# ZigBee.net
KiCad netlist of a schematic drawn in Altium Designer
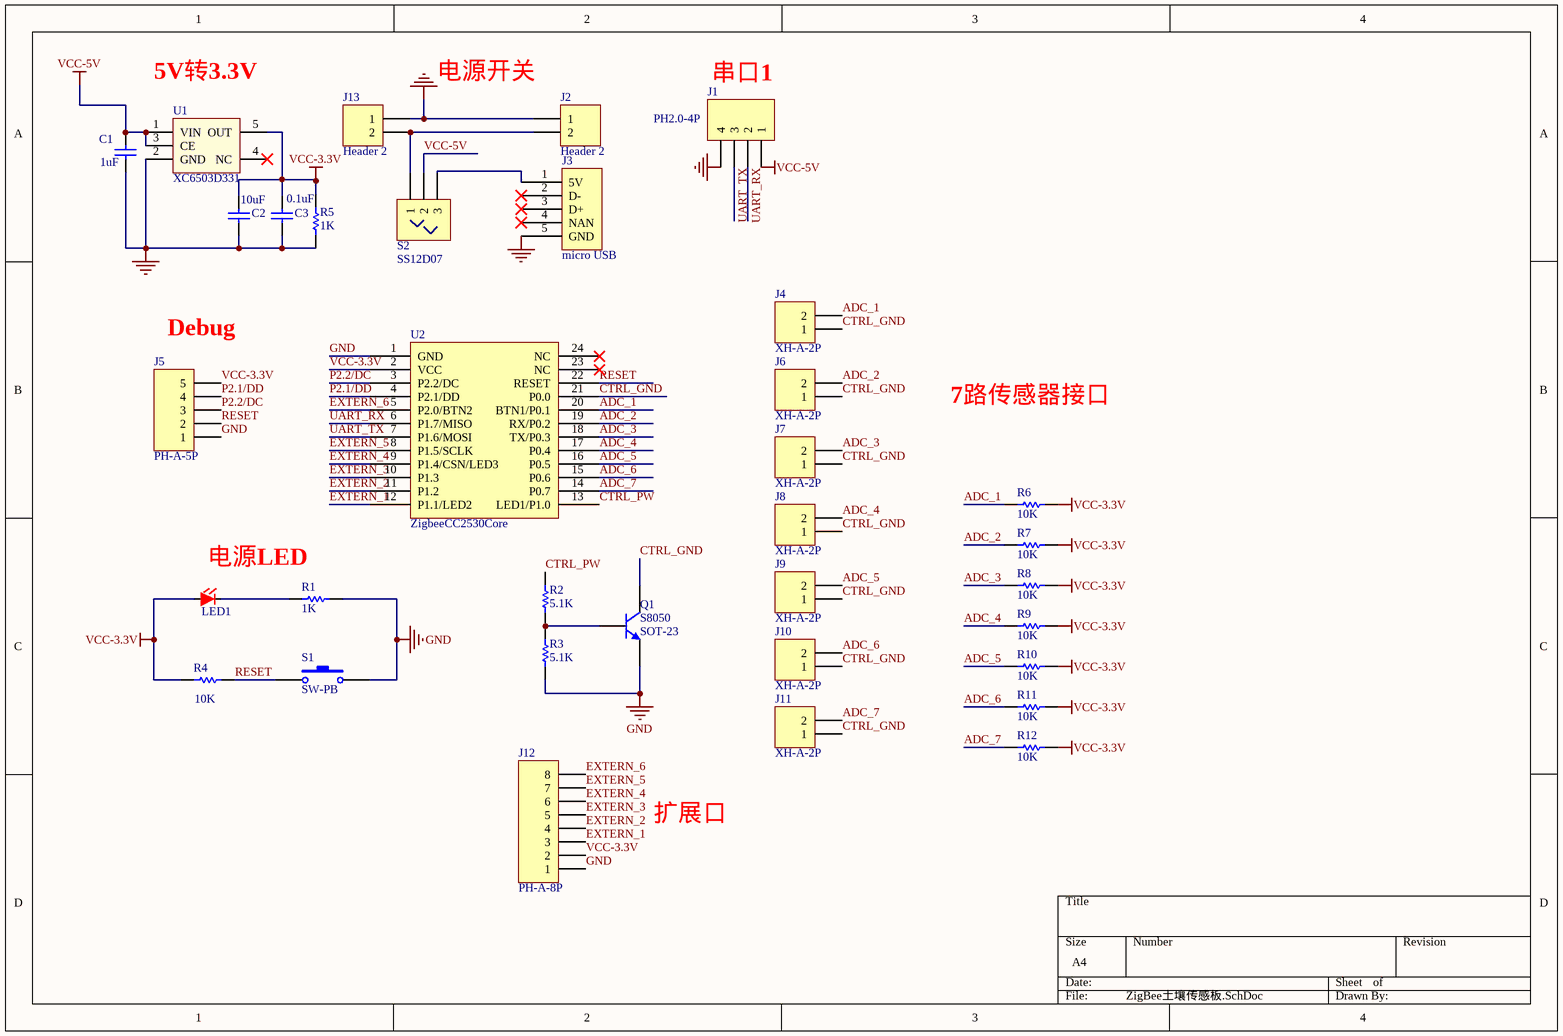
[diagram p0: ZigBee土壤传感板.SchDoc]

(export (version "E")
  (design (tool "Eeschema 10.0.6"))
  (components
    (comp (ref "C1")
      (value "1uF")
      (footprint "C0805_M2013")
      (description "Capacitor")
      (fields (field (name "PUBLISHER") "Altium Limited"))
      (libsource (lib "Miscellaneous Devices") (part "Cap"))
    )
    (comp (ref "C2")
      (value "10uF")
      (footprint "C0805_M2013")
      (description "Capacitor")
      (fields (field (name "PUBLISHER") "Altium Limited"))
      (libsource (lib "Miscellaneous Devices") (part "Cap"))
    )
    (comp (ref "C3")
      (value "0.1uF")
      (footprint "C0805_M2013")
      (description "Capacitor")
      (fields (field (name "PUBLISHER") "Altium Limited"))
      (libsource (lib "Miscellaneous Devices") (part "Cap"))
    )
    (comp (ref "J1")
      (value "PH2.0-4P")
      (footprint "PH2.0-4P")
      (description "Header, 4-Pin")
      (fields (field (name "PUBLISHER") "Altium Limited"))
      (libsource (lib "Miscellaneous Connectors") (part "Header 4"))
    )
    (comp (ref "J2")
      (value "Header 2")
      (footprint "18650")
      (description "Header, 2-Pin")
      (fields (field (name "PUBLISHER") "Altium Limited"))
      (libsource (lib "") (part "Header 2_1"))
    )
    (comp (ref "J3")
      (value "micro USB")
      (footprint "MICRO-USB")
      (description "micro USB母")
      (libsource (lib "Liyao原理图库") (part "micro USB"))
    )
    (comp (ref "J4")
      (value "XH-A-2P")
      (footprint "XH-A-2P")
      (description "Header, 2.5mm,2-Pin")
      (libsource (lib "7.PH XH VH KF2510连接器原理库") (part "XH-A-2P"))
    )
    (comp (ref "J5")
      (value "PH-A-5P")
      (footprint "PH-A-5P")
      (description "Header, 2.0mm,5-Pin")
      (libsource (lib "7.PH XH VH KF2510连接器原理库") (part "PH-A-5P"))
    )
    (comp (ref "J6")
      (value "XH-A-2P")
      (footprint "XH-A-2P")
      (description "Header, 2.5mm,2-Pin")
      (libsource (lib "7.PH XH VH KF2510连接器原理库") (part "XH-A-2P"))
    )
    (comp (ref "J7")
      (value "XH-A-2P")
      (footprint "XH-A-2P")
      (description "Header, 2.5mm,2-Pin")
      (libsource (lib "7.PH XH VH KF2510连接器原理库") (part "XH-A-2P"))
    )
    (comp (ref "J8")
      (value "XH-A-2P")
      (footprint "XH-A-2P")
      (description "Header, 2.5mm,2-Pin")
      (libsource (lib "7.PH XH VH KF2510连接器原理库") (part "XH-A-2P"))
    )
    (comp (ref "J9")
      (value "XH-A-2P")
      (footprint "XH-A-2P")
      (description "Header, 2.5mm,2-Pin")
      (libsource (lib "7.PH XH VH KF2510连接器原理库") (part "XH-A-2P"))
    )
    (comp (ref "J10")
      (value "XH-A-2P")
      (footprint "XH-A-2P")
      (description "Header, 2.5mm,2-Pin")
      (libsource (lib "7.PH XH VH KF2510连接器原理库") (part "XH-A-2P"))
    )
    (comp (ref "J11")
      (value "XH-A-2P")
      (footprint "XH-A-2P")
      (description "Header, 2.5mm,2-Pin")
      (libsource (lib "7.PH XH VH KF2510连接器原理库") (part "XH-A-2P"))
    )
    (comp (ref "J12")
      (value "PH-A-8P")
      (footprint "XH-A-8P")
      (description "Header, 2.0mm,8-Pin")
      (libsource (lib "7.PH XH VH KF2510连接器原理库") (part "PH-A-8P"))
    )
    (comp (ref "J13")
      (value "Header 2")
      (footprint "XH-A-2P")
      (description "Header, 2-Pin")
      (fields (field (name "PUBLISHER") "Altium Limited"))
      (libsource (lib "Miscellaneous Connectors") (part "Header 2"))
    )
    (comp (ref "LED1")
      (value "LED-R")
      (footprint "0805_LED")
      (description "LED红")
      (libsource (lib "Liyao原理图库") (part "LED-R"))
    )
    (comp (ref "Q1")
      (value "SOT-23")
      (footprint "SOT-23-3")
      (description "NPN Bipolar Transistor")
      (fields (field (name "ALTIUM_VALUE") "S8050") (field (name "PUBLISHER") "Altium Limited"))
      (libsource (lib "CYSchlib") (part "NPN"))
    )
    (comp (ref "R1")
      (value "1K")
      (footprint "R0805_M2013")
      (description "Resistor")
      (fields (field (name "Comment") "R0805_M2013"))
      (libsource (lib "1.电阻、电容、电感原理库") (part "R0805_M2013"))
    )
    (comp (ref "R2")
      (value "5.1K")
      (footprint "R0805_M2013")
      (description "Resistor")
      (fields (field (name "PUBLISHER") "Altium Limited"))
      (libsource (lib "Miscellaneous Devices") (part "Res1"))
    )
    (comp (ref "R3")
      (value "5.1K")
      (footprint "R0805_M2013")
      (description "Resistor")
      (fields (field (name "PUBLISHER") "Altium Limited"))
      (libsource (lib "Miscellaneous Devices") (part "Res1"))
    )
    (comp (ref "R4")
      (value "10K")
      (footprint "R0805_M2013")
      (description "Resistor")
      (fields (field (name "Comment") "R0805_M2013"))
      (libsource (lib "1.电阻、电容、电感原理库") (part "R0805_M2013"))
    )
    (comp (ref "R5")
      (value "1K")
      (footprint "R0805_M2013")
      (description "Resistor")
      (fields (field (name "PUBLISHER") "Altium Limited"))
      (libsource (lib "Miscellaneous Devices") (part "Res1"))
    )
    (comp (ref "R6")
      (value "10K")
      (footprint "R0805_M2013")
      (description "Resistor")
      (fields (field (name "PUBLISHER") "Altium Limited"))
      (libsource (lib "Miscellaneous Devices") (part "Res1"))
    )
    (comp (ref "R7")
      (value "10K")
      (footprint "R0805_M2013")
      (description "Resistor")
      (fields (field (name "PUBLISHER") "Altium Limited"))
      (libsource (lib "Miscellaneous Devices") (part "Res1"))
    )
    (comp (ref "R8")
      (value "10K")
      (footprint "R0805_M2013")
      (description "Resistor")
      (fields (field (name "PUBLISHER") "Altium Limited"))
      (libsource (lib "Miscellaneous Devices") (part "Res1"))
    )
    (comp (ref "R9")
      (value "10K")
      (footprint "R0805_M2013")
      (description "Resistor")
      (fields (field (name "PUBLISHER") "Altium Limited"))
      (libsource (lib "Miscellaneous Devices") (part "Res1"))
    )
    (comp (ref "R10")
      (value "10K")
      (footprint "R0805_M2013")
      (description "Resistor")
      (fields (field (name "PUBLISHER") "Altium Limited"))
      (libsource (lib "Miscellaneous Devices") (part "Res1"))
    )
    (comp (ref "R11")
      (value "10K")
      (footprint "R0805_M2013")
      (description "Resistor")
      (fields (field (name "PUBLISHER") "Altium Limited"))
      (libsource (lib "Miscellaneous Devices") (part "Res1"))
    )
    (comp (ref "R12")
      (value "10K")
      (footprint "R0805_M2013")
      (description "Resistor")
      (fields (field (name "PUBLISHER") "Altium Limited"))
      (libsource (lib "Miscellaneous Devices") (part "Res1"))
    )
    (comp (ref "S1")
      (value "SW-PB")
      (footprint "SW-KEY")
      (description "Switch")
      (fields (field (name "PUBLISHER") "Altium Limited"))
      (libsource (lib "Miscellaneous Devices") (part "SW-PB"))
    )
    (comp (ref "S2") (value "SS12D07") (footprint "SS-12D07") (libsource (lib "Liyao原理图库") (part "SS12D07")))
    (comp (ref "U1")
      (value "XC6503D331")
      (footprint "SOT23-5")
      (libsource (lib "CYSchlib") (part "XC6503Dxxx"))
    )
    (comp (ref "U2")
      (value "ZigbeeCC2530Core")
      (footprint "CC2530_CORE")
      (libsource (lib "Liyao原理图库") (part "ZigbeeCC2530Core"))
    )
  )
  (nets
    (net (code "1") (name "/ADC_1") (class "Default")
      (node (ref "J4") (pin "2") (pinfunction "2_2") (pintype "passive"))
      (node (ref "R6") (pin "2") (pinfunction "2_2") (pintype "passive"))
      (node (ref "U2") (pin "20") (pinfunction "BTN1/P0.1_20") (pintype "passive"))
    )
    (net (code "2") (name "/ADC_2") (class "Default")
      (node (ref "J6") (pin "2") (pinfunction "2_2") (pintype "passive"))
      (node (ref "R7") (pin "2") (pinfunction "2_2") (pintype "passive"))
      (node (ref "U2") (pin "19") (pinfunction "RX/P0.2_19") (pintype "passive"))
    )
    (net (code "3") (name "/ADC_3") (class "Default")
      (node (ref "J7") (pin "2") (pinfunction "2_2") (pintype "passive"))
      (node (ref "R8") (pin "2") (pinfunction "2_2") (pintype "passive"))
      (node (ref "U2") (pin "18") (pinfunction "TX/P0.3_18") (pintype "passive"))
    )
    (net (code "4") (name "/ADC_4") (class "Default")
      (node (ref "J8") (pin "2") (pinfunction "2_2") (pintype "passive"))
      (node (ref "R9") (pin "2") (pinfunction "2_2") (pintype "passive"))
      (node (ref "U2") (pin "17") (pinfunction "P0.4_17") (pintype "passive"))
    )
    (net (code "5") (name "/ADC_5") (class "Default")
      (node (ref "J9") (pin "2") (pinfunction "2_2") (pintype "passive"))
      (node (ref "R10") (pin "2") (pinfunction "2_2") (pintype "passive"))
      (node (ref "U2") (pin "16") (pinfunction "P0.5_16") (pintype "passive"))
    )
    (net (code "6") (name "/ADC_6") (class "Default")
      (node (ref "J10") (pin "2") (pinfunction "2_2") (pintype "passive"))
      (node (ref "R11") (pin "2") (pinfunction "2_2") (pintype "passive"))
      (node (ref "U2") (pin "15") (pinfunction "P0.6_15") (pintype "passive"))
    )
    (net (code "7") (name "/ADC_7") (class "Default")
      (node (ref "J11") (pin "2") (pinfunction "2_2") (pintype "passive"))
      (node (ref "R12") (pin "2") (pinfunction "2_2") (pintype "passive"))
      (node (ref "U2") (pin "14") (pinfunction "P0.7_14") (pintype "passive"))
    )
    (net (code "8") (name "/CTRL_GND") (class "Default")
      (node (ref "J10") (pin "1") (pinfunction "1_1") (pintype "passive"))
      (node (ref "J11") (pin "1") (pinfunction "1_1") (pintype "passive"))
      (node (ref "J4") (pin "1") (pinfunction "1_1") (pintype "passive"))
      (node (ref "J6") (pin "1") (pinfunction "1_1") (pintype "passive"))
      (node (ref "J7") (pin "1") (pinfunction "1_1") (pintype "passive"))
      (node (ref "J8") (pin "1") (pinfunction "1_1") (pintype "passive"))
      (node (ref "J9") (pin "1") (pinfunction "1_1") (pintype "passive"))
      (node (ref "Q1") (pin "3") (pinfunction "C_3") (pintype "passive"))
      (node (ref "U2") (pin "21") (pinfunction "P0.0_21") (pintype "passive"))
    )
    (net (code "9") (name "/CTRL_PW") (class "Default")
      (node (ref "R2") (pin "1") (pinfunction "1_1") (pintype "passive"))
      (node (ref "U2") (pin "13") (pinfunction "LED1/P1.0_13") (pintype "passive"))
    )
    (net (code "10") (name "/EXTERN_1") (class "Default")
      (node (ref "J12") (pin "3") (pinfunction "3_3") (pintype "passive"))
      (node (ref "U2") (pin "12") (pinfunction "P1.1/LED2_12") (pintype "passive"))
    )
    (net (code "11") (name "/EXTERN_2") (class "Default")
      (node (ref "J12") (pin "4") (pinfunction "4_4") (pintype "passive"))
      (node (ref "U2") (pin "11") (pinfunction "P1.2_11") (pintype "passive"))
    )
    (net (code "12") (name "/EXTERN_3") (class "Default")
      (node (ref "J12") (pin "5") (pinfunction "5_5") (pintype "passive"))
      (node (ref "U2") (pin "10") (pinfunction "P1.3_10") (pintype "passive"))
    )
    (net (code "13") (name "/EXTERN_4") (class "Default")
      (node (ref "J12") (pin "6") (pinfunction "6_6") (pintype "passive"))
      (node (ref "U2") (pin "9") (pinfunction "P1.4/CSN/LED3_9") (pintype "passive"))
    )
    (net (code "14") (name "/EXTERN_5") (class "Default")
      (node (ref "J12") (pin "7") (pinfunction "7_7") (pintype "passive"))
      (node (ref "U2") (pin "8") (pinfunction "P1.5/SCLK_8") (pintype "passive"))
    )
    (net (code "15") (name "/EXTERN_6") (class "Default")
      (node (ref "J12") (pin "8") (pinfunction "8_8") (pintype "passive"))
      (node (ref "U2") (pin "5") (pinfunction "P2.0/BTN2_5") (pintype "passive"))
    )
    (net (code "16") (name "/P2.1{slash}DD") (class "Default")
      (node (ref "J5") (pin "4") (pinfunction "4_4") (pintype "passive"))
      (node (ref "U2") (pin "4") (pinfunction "P2.1/DD_4") (pintype "passive"))
    )
    (net (code "17") (name "/P2.2{slash}DC") (class "Default")
      (node (ref "J5") (pin "3") (pinfunction "3_3") (pintype "passive"))
      (node (ref "U2") (pin "3") (pinfunction "P2.2/DC_3") (pintype "passive"))
    )
    (net (code "18") (name "/RESET") (class "Default")
      (node (ref "J5") (pin "2") (pinfunction "2_2") (pintype "passive"))
      (node (ref "R4") (pin "2") (pinfunction "2_2") (pintype "passive"))
      (node (ref "S1") (pin "1") (pinfunction "1_1") (pintype "passive"))
      (node (ref "U2") (pin "22") (pinfunction "RESET_22") (pintype "passive"))
    )
    (net (code "19") (name "/UART_RX") (class "Default")
      (node (ref "J1") (pin "2") (pinfunction "2_2") (pintype "passive"))
      (node (ref "U2") (pin "6") (pinfunction "P1.7/MISO_6") (pintype "passive"))
    )
    (net (code "20") (name "/UART_TX") (class "Default")
      (node (ref "J1") (pin "3") (pinfunction "3_3") (pintype "passive"))
      (node (ref "U2") (pin "7") (pinfunction "P1.6/MOSI_7") (pintype "passive"))
    )
    (net (code "21") (name "GND") (class "Default")
      (node (ref "C1") (pin "1") (pinfunction "1_1") (pintype "passive"))
      (node (ref "C2") (pin "2") (pinfunction "2_2") (pintype "passive"))
      (node (ref "C3") (pin "2") (pinfunction "2_2") (pintype "passive"))
      (node (ref "J1") (pin "4") (pinfunction "4_4") (pintype "passive"))
      (node (ref "J12") (pin "1") (pinfunction "1_1") (pintype "passive"))
      (node (ref "J13") (pin "1") (pinfunction "1_1") (pintype "passive"))
      (node (ref "J2") (pin "1") (pinfunction "1_1") (pintype "passive"))
      (node (ref "J3") (pin "5") (pinfunction "GND_5") (pintype "passive"))
      (node (ref "J5") (pin "1") (pinfunction "1_1") (pintype "passive"))
      (node (ref "Q1") (pin "2") (pinfunction "E_2") (pintype "passive"))
      (node (ref "R1") (pin "2") (pinfunction "2_2") (pintype "passive"))
      (node (ref "R3") (pin "2") (pinfunction "2_2") (pintype "passive"))
      (node (ref "R5") (pin "1") (pinfunction "1_1") (pintype "passive"))
      (node (ref "S1") (pin "2") (pinfunction "2_2") (pintype "passive"))
      (node (ref "U1") (pin "2") (pinfunction "GND_2") (pintype "passive"))
      (node (ref "U2") (pin "1") (pinfunction "GND_1") (pintype "passive"))
    )
    (net (code "22") (name "Net-(J3-5V)") (class "Default")
      (node (ref "J3") (pin "1") (pinfunction "5V_1") (pintype "power_in"))
      (node (ref "S2") (pin "3") (pinfunction "3_3") (pintype "passive"))
    )
    (net (code "23") (name "Net-(J13-Pad2)") (class "Default")
      (node (ref "J13") (pin "2") (pinfunction "2_2") (pintype "passive"))
      (node (ref "J2") (pin "2") (pinfunction "2_2") (pintype "passive"))
      (node (ref "S2") (pin "1") (pinfunction "1_1") (pintype "passive"))
    )
    (net (code "24") (name "Net-(LED1-Pad2)") (class "Default")
      (node (ref "LED1") (pin "2") (pinfunction "2_2") (pintype "passive"))
      (node (ref "R1") (pin "1") (pinfunction "1_1") (pintype "passive"))
    )
    (net (code "25") (name "Net-(Q1-B)") (class "Default")
      (node (ref "Q1") (pin "1") (pinfunction "B_1") (pintype "passive"))
      (node (ref "R2") (pin "2") (pinfunction "2_2") (pintype "passive"))
      (node (ref "R3") (pin "1") (pinfunction "1_1") (pintype "passive"))
    )
    (net (code "26") (name "VCC-3.3V") (class "Default")
      (node (ref "C2") (pin "1") (pinfunction "1_1") (pintype "passive"))
      (node (ref "C3") (pin "1") (pinfunction "1_1") (pintype "passive"))
      (node (ref "J12") (pin "2") (pinfunction "2_2") (pintype "passive"))
      (node (ref "J5") (pin "5") (pinfunction "5_5") (pintype "passive"))
      (node (ref "LED1") (pin "1") (pinfunction "1_1") (pintype "passive"))
      (node (ref "R10") (pin "1") (pinfunction "1_1") (pintype "passive"))
      (node (ref "R11") (pin "1") (pinfunction "1_1") (pintype "passive"))
      (node (ref "R12") (pin "1") (pinfunction "1_1") (pintype "passive"))
      (node (ref "R4") (pin "1") (pinfunction "1_1") (pintype "passive"))
      (node (ref "R5") (pin "2") (pinfunction "2_2") (pintype "passive"))
      (node (ref "R6") (pin "1") (pinfunction "1_1") (pintype "passive"))
      (node (ref "R7") (pin "1") (pinfunction "1_1") (pintype "passive"))
      (node (ref "R8") (pin "1") (pinfunction "1_1") (pintype "passive"))
      (node (ref "R9") (pin "1") (pinfunction "1_1") (pintype "passive"))
      (node (ref "U1") (pin "5") (pinfunction "OUT_5") (pintype "passive"))
      (node (ref "U2") (pin "2") (pinfunction "VCC_2") (pintype "passive"))
    )
    (net (code "27") (name "VCC-5V") (class "Default")
      (node (ref "C1") (pin "2") (pinfunction "2_2") (pintype "passive"))
      (node (ref "J1") (pin "1") (pinfunction "1_1") (pintype "passive"))
      (node (ref "S2") (pin "2") (pinfunction "2_2") (pintype "passive"))
      (node (ref "U1") (pin "1") (pinfunction "VIN_1") (pintype "passive"))
      (node (ref "U1") (pin "3") (pinfunction "CE_3") (pintype "passive"))
    )
    (net (code "28") (name "unconnected-(J3-D+-Pad3)") (class "Default")
      (node (ref "J3") (pin "3") (pinfunction "D+_3") (pintype "passive+no_connect"))
    )
    (net (code "29") (name "unconnected-(J3-D--Pad2)") (class "Default")
      (node (ref "J3") (pin "2") (pinfunction "D-_2") (pintype "passive+no_connect"))
    )
    (net (code "30") (name "unconnected-(J3-NAN-Pad4)") (class "Default")
      (node (ref "J3") (pin "4") (pinfunction "NAN_4") (pintype "passive+no_connect"))
    )
    (net (code "31") (name "unconnected-(U1-NC-Pad4)") (class "Default")
      (node (ref "U1") (pin "4") (pinfunction "NC_4") (pintype "passive+no_connect"))
    )
    (net (code "32") (name "unconnected-(U2-NC-Pad23)") (class "Default")
      (node (ref "U2") (pin "23") (pinfunction "NC_23") (pintype "passive+no_connect"))
    )
    (net (code "33") (name "unconnected-(U2-NC-Pad24)") (class "Default")
      (node (ref "U2") (pin "24") (pinfunction "NC_24") (pintype "passive+no_connect"))
    )
  )
)
